# MCU.net
KiCad netlist of a schematic drawn in Altium Designer
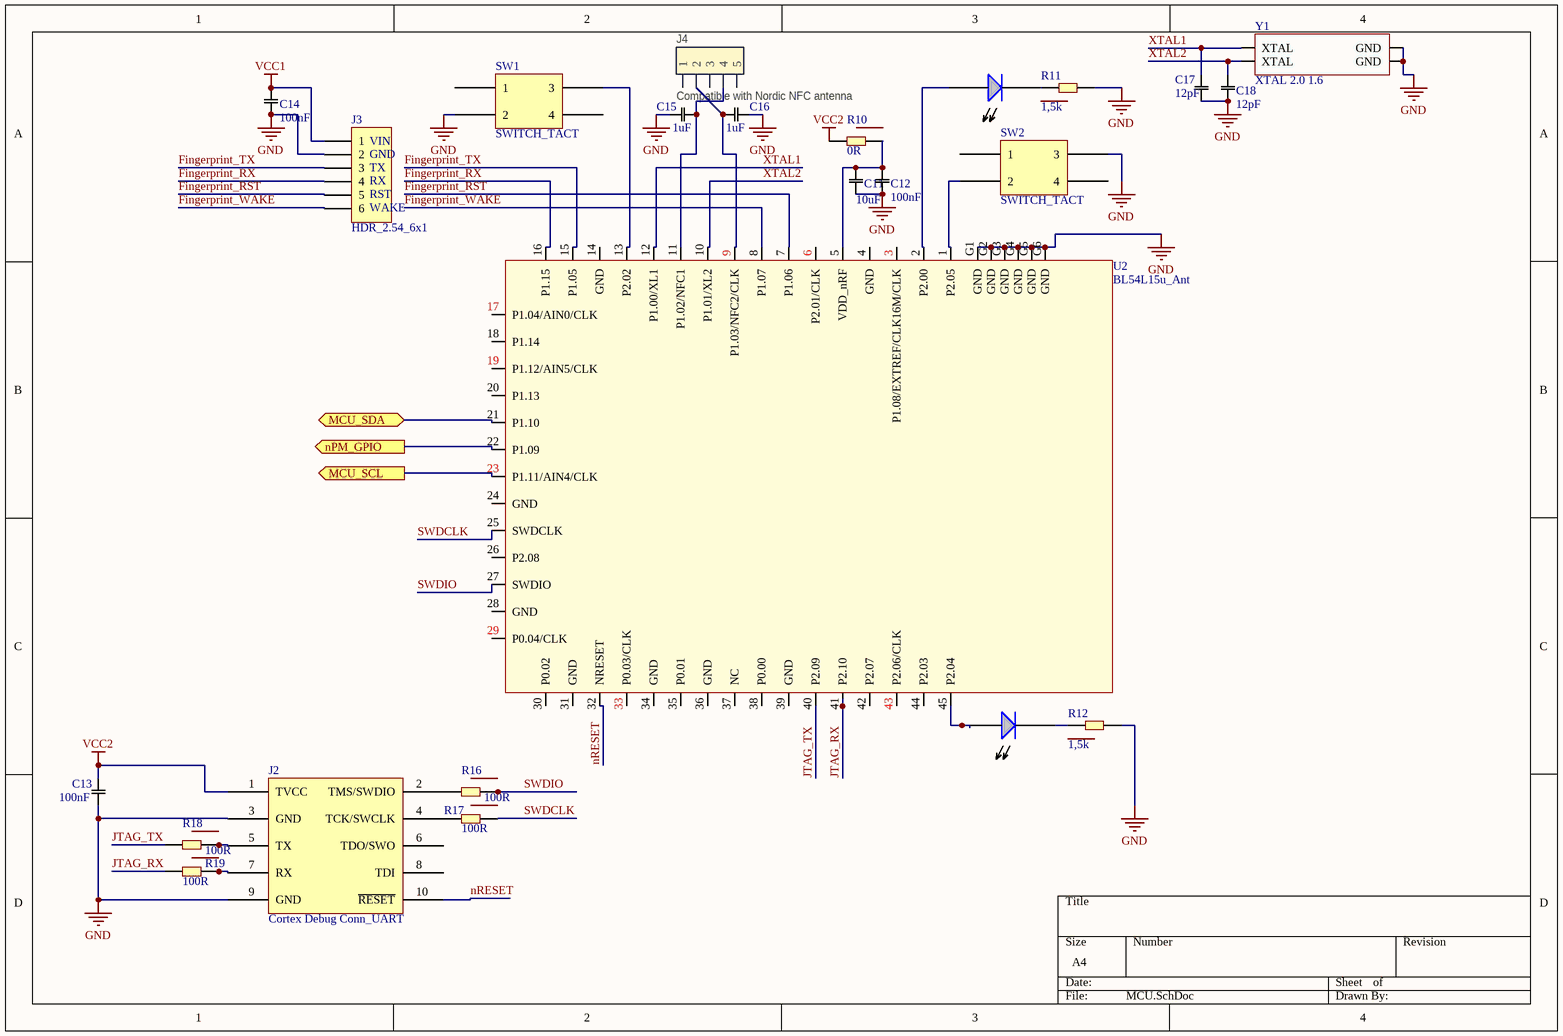
[diagram p0: MCU.SchDoc]

(export (version "E")
  (design (tool "Eeschema 10.0.6"))
  (components
    (comp (ref "C11")
      (value "10uF")
      (footprint "0402C")
      (description "Capacitor")
      (libsource (lib "basic_lib_v10") (part "C"))
    )
    (comp (ref "C12")
      (value "100nF")
      (footprint "0402C")
      (description "Capacitor")
      (libsource (lib "basic_lib_v10") (part "C"))
    )
    (comp (ref "C13")
      (value "100nF")
      (footprint "0402C")
      (description "Capacitor")
      (libsource (lib "basic_lib_v10") (part "C"))
    )
    (comp (ref "C14")
      (value "100nF")
      (footprint "0402C")
      (description "Capacitor")
      (libsource (lib "basic_lib_v10") (part "C"))
    )
    (comp (ref "C15")
      (value "1uF")
      (footprint "0402C")
      (description "Capacitor")
      (libsource (lib "basic_lib_v10") (part "C"))
    )
    (comp (ref "C16")
      (value "1uF")
      (footprint "0402C")
      (description "Capacitor")
      (libsource (lib "basic_lib_v10") (part "C"))
    )
    (comp (ref "C17")
      (value "12pF")
      (footprint "0402C")
      (description "Capacitor")
      (libsource (lib "basic_lib_v10") (part "C"))
    )
    (comp (ref "C18")
      (value "12pF")
      (footprint "0402C")
      (description "Capacitor")
      (libsource (lib "basic_lib_v10") (part "C"))
    )
    (comp (ref "D11") (value "LED") (footprint "0603LED_RED") (libsource (lib "basic_lib_v10") (part "LED")))
    (comp (ref "D12") (value "LED") (footprint "0603LED_RED") (libsource (lib "basic_lib_v10") (part "LED")))
    (comp (ref "J2")
      (value "Cortex Debug Conn_UART")
      (footprint "Cortex Debug Connector - THT")
      (description "JTAG10 Connector")
      (libsource (lib "basic_lib_v10") (part "Cortex Debug Conn_UART"))
    )
    (comp (ref "J3")
      (value "HDR_2.54_6x1")
      (footprint "HDR 2.54MM 1x6")
      (description "Header 2.54, 6-Pin")
      (fields (field (name "PUBLISHER") "Altium Limited"))
      (libsource (lib "basic_lib_v10") (part "HDR_2.54_6x1"))
    )
    (comp (ref "J4")
      (value "Compatible with Nordic NFC antenna")
      (footprint "FPC_05P-0.5mm-RA-SMD")
      (description "0.5mm FPC, 5P,Right Angle SMT,Double Contact,H=1.2mm,White, Tin plated")
      (fields
        (field (name "PART NUMBER") "FPC_05P-0.5mm-RA-SMD")
        (field (name "MANUFACTURER") "WCON")
        (field (name "AUTHOR") "rsk")
      )
      (libsource (lib "basic_lib_v10") (part "NFC_CONN"))
    )
    (comp (ref "R10")
      (value "0R")
      (footprint "0402R")
      (description "Resistor")
      (libsource (lib "basic_lib_v10") (part "R"))
    )
    (comp (ref "R11")
      (value "1,5k")
      (footprint "0402R")
      (description "Resistor")
      (libsource (lib "") (part "R_1"))
    )
    (comp (ref "R12")
      (value "1,5k")
      (footprint "0402R")
      (description "Resistor")
      (libsource (lib "") (part "R_1"))
    )
    (comp (ref "R16")
      (value "100R")
      (footprint "0402R")
      (description "Resistor")
      (libsource (lib "basic_lib_v10") (part "R"))
    )
    (comp (ref "R17")
      (value "100R")
      (footprint "0402R")
      (description "Resistor")
      (libsource (lib "basic_lib_v10") (part "R"))
    )
    (comp (ref "R18")
      (value "100R")
      (footprint "0402R")
      (description "Resistor")
      (libsource (lib "basic_lib_v10") (part "R"))
    )
    (comp (ref "R19")
      (value "100R")
      (footprint "0402R")
      (description "Resistor")
      (libsource (lib "basic_lib_v10") (part "R"))
    )
    (comp (ref "SW1")
      (value "SWITCH_TACT")
      (footprint "TACT - SMD")
      (description "Switch tact")
      (libsource (lib "basic_lib_v10") (part "SWITCH_TACT"))
    )
    (comp (ref "SW2")
      (value "SWITCH_TACT")
      (footprint "TACT - SMD")
      (description "Switch tact")
      (libsource (lib "basic_lib_v10") (part "SWITCH_TACT"))
    )
    (comp (ref "U2")
      (value "BL54L15u_Ant")
      (footprint "Ezurio, BL54L15u Module, Antenna, Platform Side")
      (description "453-00223_BL54L15u_Chip ANT_SCH_Symbol_Altium")
      (libsource (lib "basic_lib_v10") (part "BL54L15u_Ant"))
    )
    (comp (ref "Y1")
      (value "XTAL 2.0 1.6")
      (footprint "XTAL 2.0 1.6")
      (description "XTAL")
      (libsource (lib "basic_lib_v10") (part "XTAL 2.0 1.6"))
    )
  )
  (nets
    (net (code "1") (name "/Fingerprint_RST") (class "Default")
      (node (ref "J3") (pin "5") (pinfunction "5_5") (pintype "passive"))
      (node (ref "U2") (pin "7") (pinfunction "P1.06_7") (pintype "passive"))
    )
    (net (code "2") (name "/Fingerprint_RX") (class "Default")
      (node (ref "J3") (pin "4") (pinfunction "4_4") (pintype "passive"))
      (node (ref "U2") (pin "16") (pinfunction "P1.15_16") (pintype "passive"))
    )
    (net (code "3") (name "/Fingerprint_TX") (class "Default")
      (node (ref "J3") (pin "3") (pinfunction "3_3") (pintype "passive"))
      (node (ref "U2") (pin "15") (pinfunction "P1.05_15") (pintype "passive"))
    )
    (net (code "4") (name "/Fingerprint_WAKE") (class "Default")
      (node (ref "J3") (pin "6") (pinfunction "6_6") (pintype "passive"))
      (node (ref "U2") (pin "8") (pinfunction "P1.07_8") (pintype "passive"))
    )
    (net (code "5") (name "/JTAG_RX") (class "Default")
      (node (ref "R19") (pin "1") (pintype "passive"))
      (node (ref "U2") (pin "41") (pinfunction "P2.10_41") (pintype "passive"))
    )
    (net (code "6") (name "/JTAG_TX") (class "Default")
      (node (ref "R18") (pin "1") (pintype "passive"))
      (node (ref "U2") (pin "40") (pinfunction "P2.09_40") (pintype "passive"))
    )
    (net (code "7") (name "/MCU_SCL") (class "Default")
      (node (ref "U2") (pin "23") (pinfunction "P1.11/AIN4/CLK_23") (pintype "passive"))
    )
    (net (code "8") (name "/MCU_SDA") (class "Default")
      (node (ref "U2") (pin "21") (pinfunction "P1.10_21") (pintype "passive"))
    )
    (net (code "9") (name "/SWDCLK") (class "Default")
      (node (ref "R17") (pin "2") (pintype "passive"))
      (node (ref "U2") (pin "25") (pinfunction "SWDCLK_25") (pintype "passive"))
    )
    (net (code "10") (name "/SWDIO") (class "Default")
      (node (ref "R16") (pin "2") (pintype "passive"))
      (node (ref "U2") (pin "27") (pinfunction "SWDIO_27") (pintype "passive"))
    )
    (net (code "11") (name "/XTAL1") (class "Default")
      (node (ref "C17") (pin "1") (pintype "passive"))
      (node (ref "U2") (pin "12") (pinfunction "P1.00/XL1_12") (pintype "passive"))
      (node (ref "Y1") (pin "3") (pinfunction "XTAL_3") (pintype "passive"))
    )
    (net (code "12") (name "/XTAL2") (class "Default")
      (node (ref "C18") (pin "1") (pintype "passive"))
      (node (ref "U2") (pin "10") (pinfunction "P1.01/XL2_10") (pintype "passive"))
      (node (ref "Y1") (pin "1") (pinfunction "XTAL_1") (pintype "passive"))
    )
    (net (code "13") (name "/nPM_GPIO") (class "Default")
      (node (ref "U2") (pin "22") (pinfunction "P1.09_22") (pintype "passive"))
    )
    (net (code "14") (name "/nRESET") (class "Default")
      (node (ref "J2") (pin "10") (pinfunction "~{RESET}_10") (pintype "passive"))
      (node (ref "U2") (pin "32") (pinfunction "NRESET_32") (pintype "passive"))
    )
    (net (code "15") (name "GND") (class "Default")
      (node (ref "C11") (pin "2") (pintype "passive"))
      (node (ref "C12") (pin "2") (pintype "passive"))
      (node (ref "C13") (pin "1") (pintype "passive"))
      (node (ref "C14") (pin "1") (pintype "passive"))
      (node (ref "C15") (pin "1") (pintype "passive"))
      (node (ref "C16") (pin "2") (pintype "passive"))
      (node (ref "C17") (pin "2") (pintype "passive"))
      (node (ref "C18") (pin "2") (pintype "passive"))
      (node (ref "J2") (pin "3") (pinfunction "GND_3") (pintype "passive"))
      (node (ref "J2") (pin "9") (pinfunction "GND_9") (pintype "passive"))
      (node (ref "J3") (pin "2") (pinfunction "2_2") (pintype "passive"))
      (node (ref "R11") (pin "1") (pintype "passive"))
      (node (ref "R12") (pin "1") (pintype "passive"))
      (node (ref "SW1") (pin "2") (pinfunction "2_2") (pintype "passive"))
      (node (ref "SW2") (pin "3") (pinfunction "3_3") (pintype "passive"))
      (node (ref "U2") (pin "G1") (pinfunction "GND_G1") (pintype "passive"))
      (node (ref "U2") (pin "G2") (pinfunction "GND_G2") (pintype "passive"))
      (node (ref "U2") (pin "G3") (pinfunction "GND_G3") (pintype "passive"))
      (node (ref "U2") (pin "G4") (pinfunction "GND_G4") (pintype "passive"))
      (node (ref "U2") (pin "G5") (pinfunction "GND_G5") (pintype "passive"))
      (node (ref "U2") (pin "G6") (pinfunction "GND_G6") (pintype "passive"))
      (node (ref "Y1") (pin "2") (pinfunction "GND_2") (pintype "passive"))
      (node (ref "Y1") (pin "4") (pinfunction "GND_4") (pintype "passive"))
    )
    (net (code "16") (name "Net-(D11-Pad1)") (class "Default")
      (node (ref "D11") (pin "1") (pinfunction "1_1") (pintype "passive"))
      (node (ref "R11") (pin "2") (pintype "passive"))
    )
    (net (code "17") (name "Net-(D12-Pad1)") (class "Default")
      (node (ref "D12") (pin "1") (pinfunction "1_1") (pintype "passive"))
      (node (ref "R12") (pin "2") (pintype "passive"))
    )
    (net (code "18") (name "Net-(J2-RX)") (class "Default")
      (node (ref "J2") (pin "7") (pinfunction "RX_7") (pintype "passive"))
      (node (ref "R19") (pin "2") (pintype "passive"))
    )
    (net (code "19") (name "Net-(J2-TCK{slash}SWCLK)") (class "Default")
      (node (ref "J2") (pin "4") (pinfunction "TCK/SWCLK_4") (pintype "passive"))
      (node (ref "R17") (pin "1") (pintype "passive"))
    )
    (net (code "20") (name "Net-(J2-TMS{slash}SWDIO)") (class "Default")
      (node (ref "J2") (pin "2") (pinfunction "TMS/SWDIO_2") (pintype "passive"))
      (node (ref "R16") (pin "1") (pintype "passive"))
    )
    (net (code "21") (name "Net-(J2-TX)") (class "Default")
      (node (ref "J2") (pin "5") (pinfunction "TX_5") (pintype "passive"))
      (node (ref "R18") (pin "2") (pintype "passive"))
    )
    (net (code "22") (name "Net-(U2-P1.02{slash}NFC1)") (class "Default")
      (node (ref "C15") (pin "2") (pintype "passive"))
      (node (ref "J4") (pin "4") (pinfunction "4_4") (pintype "passive"))
      (node (ref "U2") (pin "11") (pinfunction "P1.02/NFC1_11") (pintype "passive"))
    )
    (net (code "23") (name "Net-(U2-P1.03{slash}NFC2{slash}CLK)") (class "Default")
      (node (ref "C16") (pin "1") (pintype "passive"))
      (node (ref "J4") (pin "2") (pinfunction "2_2") (pintype "passive"))
      (node (ref "U2") (pin "9") (pinfunction "P1.03/NFC2/CLK_9") (pintype "passive"))
    )
    (net (code "24") (name "Net-(U2-P2.00)") (class "Default")
      (node (ref "D11") (pin "2") (pinfunction "2_2") (pintype "passive"))
      (node (ref "U2") (pin "2") (pinfunction "P2.00_2") (pintype "passive"))
    )
    (net (code "25") (name "Net-(U2-P2.02)") (class "Default")
      (node (ref "SW1") (pin "3") (pinfunction "3_3") (pintype "passive"))
      (node (ref "U2") (pin "13") (pinfunction "P2.02_13") (pintype "passive"))
    )
    (net (code "26") (name "Net-(U2-P2.04)") (class "Default")
      (node (ref "D12") (pin "2") (pinfunction "2_2") (pintype "passive"))
      (node (ref "U2") (pin "45") (pinfunction "P2.04_45") (pintype "passive"))
    )
    (net (code "27") (name "Net-(U2-P2.05)") (class "Default")
      (node (ref "SW2") (pin "2") (pinfunction "2_2") (pintype "passive"))
      (node (ref "U2") (pin "1") (pinfunction "P2.05_1") (pintype "passive"))
    )
    (net (code "28") (name "Net-(U2-VDD_nRF)") (class "Default")
      (node (ref "C11") (pin "1") (pintype "passive"))
      (node (ref "C12") (pin "1") (pintype "passive"))
      (node (ref "R10") (pin "2") (pintype "passive"))
      (node (ref "U2") (pin "5") (pinfunction "VDD_nRF_5") (pintype "passive"))
    )
    (net (code "29") (name "VCC1") (class "Default")
      (node (ref "C14") (pin "2") (pintype "passive"))
      (node (ref "J3") (pin "1") (pinfunction "1_1") (pintype "passive"))
    )
    (net (code "30") (name "VCC2") (class "Default")
      (node (ref "C13") (pin "2") (pintype "passive"))
      (node (ref "J2") (pin "1") (pinfunction "TVCC_1") (pintype "passive"))
      (node (ref "R10") (pin "1") (pintype "passive"))
    )
    (net (code "31") (name "unconnected-(J2-TDI-Pad8)") (class "Default")
      (node (ref "J2") (pin "8") (pinfunction "TDI_8") (pintype "passive"))
    )
    (net (code "32") (name "unconnected-(J2-TDO{slash}SWO-Pad6)") (class "Default")
      (node (ref "J2") (pin "6") (pinfunction "TDO/SWO_6") (pintype "passive"))
    )
    (net (code "33") (name "unconnected-(J4-Pad1)") (class "Default")
      (node (ref "J4") (pin "1") (pinfunction "1_1") (pintype "passive"))
    )
    (net (code "34") (name "unconnected-(J4-Pad3)") (class "Default")
      (node (ref "J4") (pin "3") (pinfunction "3_3") (pintype "passive"))
    )
    (net (code "35") (name "unconnected-(J4-Pad5)") (class "Default")
      (node (ref "J4") (pin "5") (pinfunction "5_5") (pintype "passive"))
    )
    (net (code "36") (name "unconnected-(SW1-Pad1)") (class "Default")
      (node (ref "SW1") (pin "1") (pinfunction "1_1") (pintype "passive"))
    )
    (net (code "37") (name "unconnected-(SW1-Pad4)") (class "Default")
      (node (ref "SW1") (pin "4") (pinfunction "4_4") (pintype "passive"))
    )
    (net (code "38") (name "unconnected-(SW2-Pad1)") (class "Default")
      (node (ref "SW2") (pin "1") (pinfunction "1_1") (pintype "passive"))
    )
    (net (code "39") (name "unconnected-(SW2-Pad4)") (class "Default")
      (node (ref "SW2") (pin "4") (pinfunction "4_4") (pintype "passive"))
    )
    (net (code "40") (name "unconnected-(U2-GND-Pad4)") (class "Default")
      (node (ref "U2") (pin "4") (pinfunction "GND_4") (pintype "passive"))
    )
    (net (code "41") (name "unconnected-(U2-GND-Pad14)") (class "Default")
      (node (ref "U2") (pin "14") (pinfunction "GND_14") (pintype "passive"))
    )
    (net (code "42") (name "unconnected-(U2-GND-Pad24)") (class "Default")
      (node (ref "U2") (pin "24") (pinfunction "GND_24") (pintype "passive"))
    )
    (net (code "43") (name "unconnected-(U2-GND-Pad28)") (class "Default")
      (node (ref "U2") (pin "28") (pinfunction "GND_28") (pintype "passive"))
    )
    (net (code "44") (name "unconnected-(U2-GND-Pad31)") (class "Default")
      (node (ref "U2") (pin "31") (pinfunction "GND_31") (pintype "passive"))
    )
    (net (code "45") (name "unconnected-(U2-GND-Pad34)") (class "Default")
      (node (ref "U2") (pin "34") (pinfunction "GND_34") (pintype "passive"))
    )
    (net (code "46") (name "unconnected-(U2-GND-Pad36)") (class "Default")
      (node (ref "U2") (pin "36") (pinfunction "GND_36") (pintype "passive"))
    )
    (net (code "47") (name "unconnected-(U2-GND-Pad39)") (class "Default")
      (node (ref "U2") (pin "39") (pinfunction "GND_39") (pintype "passive"))
    )
    (net (code "48") (name "unconnected-(U2-NC-Pad37)") (class "Default")
      (node (ref "U2") (pin "37") (pinfunction "NC_37") (pintype "passive"))
    )
    (net (code "49") (name "unconnected-(U2-P0.00-Pad38)") (class "Default")
      (node (ref "U2") (pin "38") (pinfunction "P0.00_38") (pintype "passive"))
    )
    (net (code "50") (name "unconnected-(U2-P0.01-Pad35)") (class "Default")
      (node (ref "U2") (pin "35") (pinfunction "P0.01_35") (pintype "passive"))
    )
    (net (code "51") (name "unconnected-(U2-P0.02-Pad30)") (class "Default")
      (node (ref "U2") (pin "30") (pinfunction "P0.02_30") (pintype "passive"))
    )
    (net (code "52") (name "unconnected-(U2-P0.03{slash}CLK-Pad33)") (class "Default")
      (node (ref "U2") (pin "33") (pinfunction "P0.03/CLK_33") (pintype "passive"))
    )
    (net (code "53") (name "unconnected-(U2-P0.04{slash}CLK-Pad29)") (class "Default")
      (node (ref "U2") (pin "29") (pinfunction "P0.04/CLK_29") (pintype "passive"))
    )
    (net (code "54") (name "unconnected-(U2-P1.04{slash}AIN0{slash}CLK-Pad17)") (class "Default")
      (node (ref "U2") (pin "17") (pinfunction "P1.04/AIN0/CLK_17") (pintype "passive"))
    )
    (net (code "55") (name "unconnected-(U2-P1.08{slash}EXTREF{slash}CLK16M{slash}CLK-Pad3)") (class "Default")
      (node (ref "U2") (pin "3") (pinfunction "P1.08/EXTREF/CLK16M/CLK_3") (pintype "passive"))
    )
    (net (code "56") (name "unconnected-(U2-P1.12{slash}AIN5{slash}CLK-Pad19)") (class "Default")
      (node (ref "U2") (pin "19") (pinfunction "P1.12/AIN5/CLK_19") (pintype "passive"))
    )
    (net (code "57") (name "unconnected-(U2-P1.13-Pad20)") (class "Default")
      (node (ref "U2") (pin "20") (pinfunction "P1.13_20") (pintype "passive"))
    )
    (net (code "58") (name "unconnected-(U2-P1.14-Pad18)") (class "Default")
      (node (ref "U2") (pin "18") (pinfunction "P1.14_18") (pintype "passive"))
    )
    (net (code "59") (name "unconnected-(U2-P2.01{slash}CLK-Pad6)") (class "Default")
      (node (ref "U2") (pin "6") (pinfunction "P2.01/CLK_6") (pintype "passive"))
    )
    (net (code "60") (name "unconnected-(U2-P2.03-Pad44)") (class "Default")
      (node (ref "U2") (pin "44") (pinfunction "P2.03_44") (pintype "passive"))
    )
    (net (code "61") (name "unconnected-(U2-P2.06{slash}CLK-Pad43)") (class "Default")
      (node (ref "U2") (pin "43") (pinfunction "P2.06/CLK_43") (pintype "passive"))
    )
    (net (code "62") (name "unconnected-(U2-P2.07-Pad42)") (class "Default")
      (node (ref "U2") (pin "42") (pinfunction "P2.07_42") (pintype "passive"))
    )
    (net (code "63") (name "unconnected-(U2-P2.08-Pad26)") (class "Default")
      (node (ref "U2") (pin "26") (pinfunction "P2.08_26") (pintype "passive"))
    )
  )
)
